# Wheatstone.net
KiCad netlist of a schematic drawn in EAGLE
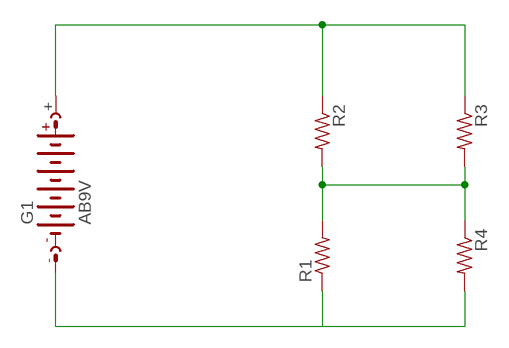
[diagram p0: schematic, sheet 1]

(export (version "E")
  (design (tool "Eeschema 10.0.6"))
  (components
    (comp (ref "G1")
      (value "AB9V")
      (footprint "eagle-import:AB9V")
      (libsource (lib "eagle-import") (part "AB9V"))
    )
    (comp (ref "R1")
      (value "R-US_R0805")
      (footprint "eagle-import:R0805")
      (libsource (lib "eagle-import") (part "R-US_R0805"))
    )
    (comp (ref "R2")
      (value "R-US_R0805")
      (footprint "eagle-import:R0805")
      (libsource (lib "eagle-import") (part "R-US_R0805"))
    )
    (comp (ref "R3")
      (value "R-US_R0805")
      (footprint "eagle-import:R0805")
      (libsource (lib "eagle-import") (part "R-US_R0805"))
    )
    (comp (ref "R4")
      (value "R-US_R0805")
      (footprint "eagle-import:R0805")
      (libsource (lib "eagle-import") (part "R-US_R0805"))
    )
  )
  (nets
    (net (code "1") (name "Net-(G1-Pad+)") (class "Default")
      (node (ref "G1") (pin "+") (pinfunction "+_+") (pintype "passive"))
      (node (ref "R2") (pin "1") (pinfunction "1_1") (pintype "passive"))
      (node (ref "R3") (pin "1") (pinfunction "1_1") (pintype "passive"))
    )
    (net (code "2") (name "Net-(G1-Pad-)") (class "Default")
      (node (ref "G1") (pin "-") (pinfunction "-_-") (pintype "passive"))
      (node (ref "R1") (pin "1") (pinfunction "1_1") (pintype "passive"))
      (node (ref "R4") (pin "2") (pinfunction "2_2") (pintype "passive"))
    )
    (net (code "3") (name "Net-(R1-Pad2)") (class "Default")
      (node (ref "R1") (pin "2") (pinfunction "2_2") (pintype "passive"))
      (node (ref "R2") (pin "2") (pinfunction "2_2") (pintype "passive"))
      (node (ref "R3") (pin "2") (pinfunction "2_2") (pintype "passive"))
      (node (ref "R4") (pin "1") (pinfunction "1_1") (pintype "passive"))
    )
  )
)
